# 1.net
KiCad netlist of a schematic drawn in Altium Designer
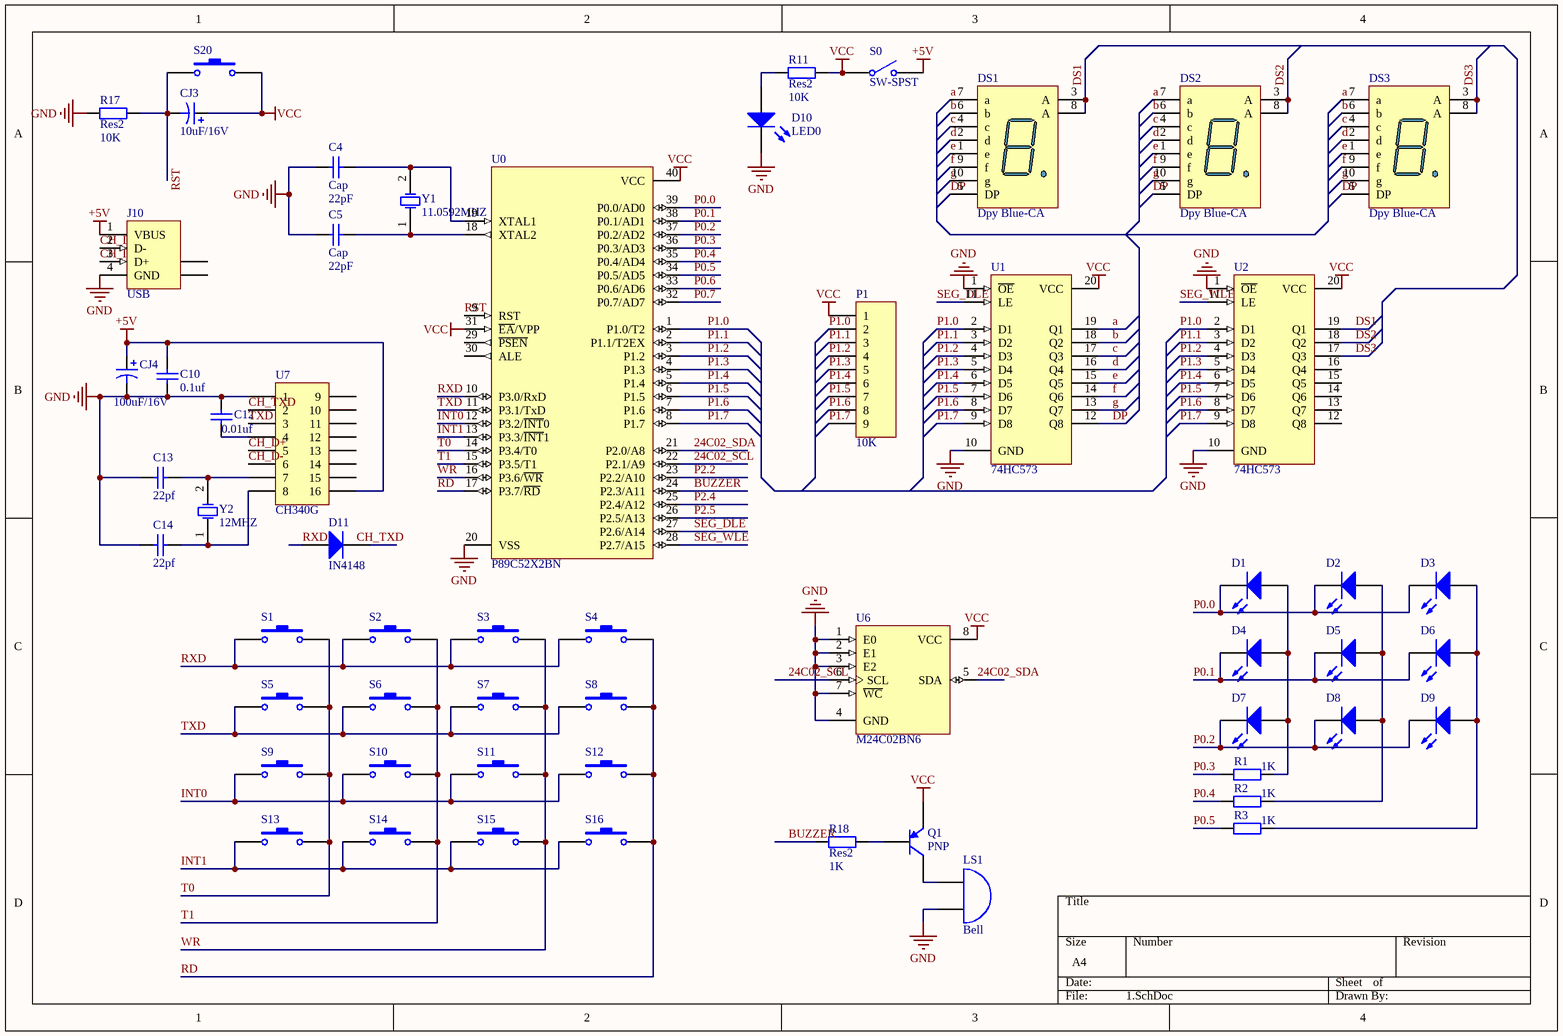
[diagram p0: 1.SchDoc]

(export (version "E")
  (design (tool "Eeschema 10.0.6"))
  (components
    (comp (ref "C4")
      (value "Cap")
      (footprint "RAD-0.3")
      (description "Capacitor")
      (fields (field (name "ALTIUM_VALUE") "22pF") (field (name "PUBLISHER") "Altium Limited"))
      (libsource (lib "Miscellaneous Devices") (part "Cap"))
    )
    (comp (ref "C5")
      (value "Cap")
      (footprint "RAD-0.3")
      (description "Capacitor")
      (fields (field (name "ALTIUM_VALUE") "22pF") (field (name "PUBLISHER") "Altium Limited"))
      (libsource (lib "Miscellaneous Devices") (part "Cap"))
    )
    (comp (ref "C10")
      (value "0.1uf")
      (footprint "RAD-0.3")
      (description "Capacitor")
      (fields (field (name "Comment") "Cap") (field (name "PUBLISHER") "Altium Limited"))
      (libsource (lib "Miscellaneous Devices") (part "Cap"))
    )
    (comp (ref "C12")
      (value "0.01uf")
      (footprint "RAD-0.3")
      (description "Capacitor")
      (fields (field (name "Comment") "Cap") (field (name "PUBLISHER") "Altium Limited"))
      (libsource (lib "Miscellaneous Devices") (part "Cap"))
    )
    (comp (ref "C13")
      (value "22pf")
      (footprint "RAD-0.3")
      (description "Capacitor")
      (fields (field (name "Comment") "Cap") (field (name "PUBLISHER") "Altium Limited"))
      (libsource (lib "Miscellaneous Devices") (part "Cap"))
    )
    (comp (ref "C14")
      (value "22pf")
      (footprint "RAD-0.3")
      (description "Capacitor")
      (fields (field (name "Comment") "Cap") (field (name "PUBLISHER") "Altium Limited"))
      (libsource (lib "Miscellaneous Devices") (part "Cap"))
    )
    (comp (ref "CJ3")
      (value "10uF/16V")
      (footprint "RB7.6-15")
      (description "Polarized Capacitor (Radial)")
      (fields (field (name "PUBLISHER") "Altium Limited"))
      (libsource (lib "Miscellaneous Devices") (part "Cap Pol1"))
    )
    (comp (ref "CJ4")
      (value "100uF/16V")
      (footprint "RB7.6-15")
      (description "Polarized Capacitor (Radial)")
      (fields (field (name "PUBLISHER") "Altium Limited"))
      (libsource (lib "Miscellaneous Devices") (part "Cap Pol1"))
    )
    (comp (ref "D1")
      (value "~")
      (footprint "LED-0")
      (description "Typical INFRARED GaAs LED")
      (fields (field (name "PUBLISHER") "Altium Limited"))
      (libsource (lib "Miscellaneous Devices") (part "LED0"))
    )
    (comp (ref "D2")
      (value "~")
      (footprint "LED-0")
      (description "Typical INFRARED GaAs LED")
      (fields (field (name "PUBLISHER") "Altium Limited"))
      (libsource (lib "Miscellaneous Devices") (part "LED0"))
    )
    (comp (ref "D3")
      (value "~")
      (footprint "LED-0")
      (description "Typical INFRARED GaAs LED")
      (fields (field (name "PUBLISHER") "Altium Limited"))
      (libsource (lib "Miscellaneous Devices") (part "LED0"))
    )
    (comp (ref "D4")
      (value "~")
      (footprint "LED-0")
      (description "Typical INFRARED GaAs LED")
      (fields (field (name "PUBLISHER") "Altium Limited"))
      (libsource (lib "Miscellaneous Devices") (part "LED0"))
    )
    (comp (ref "D5")
      (value "~")
      (footprint "LED-0")
      (description "Typical INFRARED GaAs LED")
      (fields (field (name "PUBLISHER") "Altium Limited"))
      (libsource (lib "Miscellaneous Devices") (part "LED0"))
    )
    (comp (ref "D6")
      (value "~")
      (footprint "LED-0")
      (description "Typical INFRARED GaAs LED")
      (fields (field (name "PUBLISHER") "Altium Limited"))
      (libsource (lib "Miscellaneous Devices") (part "LED0"))
    )
    (comp (ref "D7")
      (value "~")
      (footprint "LED-0")
      (description "Typical INFRARED GaAs LED")
      (fields (field (name "PUBLISHER") "Altium Limited"))
      (libsource (lib "Miscellaneous Devices") (part "LED0"))
    )
    (comp (ref "D8")
      (value "~")
      (footprint "LED-0")
      (description "Typical INFRARED GaAs LED")
      (fields (field (name "PUBLISHER") "Altium Limited"))
      (libsource (lib "Miscellaneous Devices") (part "LED0"))
    )
    (comp (ref "D9")
      (value "~")
      (footprint "LED-0")
      (description "Typical INFRARED GaAs LED")
      (fields (field (name "PUBLISHER") "Altium Limited"))
      (libsource (lib "Miscellaneous Devices") (part "LED0"))
    )
    (comp (ref "D10")
      (value "LED0")
      (footprint "LED-0")
      (description "Typical INFRARED GaAs LED")
      (fields (field (name "PUBLISHER") "Altium Limited"))
      (libsource (lib "Miscellaneous Devices") (part "LED0"))
    )
    (comp (ref "D11")
      (value "IN4148")
      (footprint "DO-35")
      (description "High Conductance Fast Diode")
      (fields (field (name "PUBLISHER") "Altium Limited"))
      (libsource (lib "Miscellaneous Devices") (part "Diode 1N914"))
    )
    (comp (ref "DS1")
      (value "Dpy Blue-CA")
      (footprint "H")
      (description "14.2 mm General Purpose Blue 7-Segment Display: CA, RH DP, Gray Surface")
      (fields (field (name "PUBLISHER") "Altium Limited"))
      (libsource (lib "Miscellaneous Devices") (part "Dpy Blue-CA"))
    )
    (comp (ref "DS2")
      (value "Dpy Blue-CA")
      (footprint "H")
      (description "14.2 mm General Purpose Blue 7-Segment Display: CA, RH DP, Gray Surface")
      (fields (field (name "PUBLISHER") "Altium Limited"))
      (libsource (lib "Miscellaneous Devices") (part "Dpy Blue-CA"))
    )
    (comp (ref "DS3")
      (value "Dpy Blue-CA")
      (footprint "H")
      (description "14.2 mm General Purpose Blue 7-Segment Display: CA, RH DP, Gray Surface")
      (fields (field (name "PUBLISHER") "Altium Limited"))
      (libsource (lib "Miscellaneous Devices") (part "Dpy Blue-CA"))
    )
    (comp (ref "J10")
      (value "USB")
      (footprint "787616")
      (description "USB 1.1, Right Angle, Thru-Hole, A Type, Receptacle, 4 Position, Natural")
      (fields (field (name "PUBLISHER") "Altium Limited"))
      (libsource (lib "AMP Serial Bus USB") (part "787616-5"))
    )
    (comp (ref "LS1")
      (value "Bell")
      (footprint "PIN2")
      (description "Electrical Bell")
      (fields (field (name "PUBLISHER") "Altium Limited"))
      (libsource (lib "Miscellaneous Devices") (part "Bell"))
    )
    (comp (ref "P1")
      (value "10K")
      (footprint "MHDR1X9")
      (description "Header, 9-Pin")
      (fields (field (name "PUBLISHER") "Altium Limited"))
      (libsource (lib "Miscellaneous Connectors") (part "MHDR1X9"))
    )
    (comp (ref "Q1")
      (value "PNP")
      (footprint "SOT-23B")
      (description "PNP Bipolar Transistor")
      (fields (field (name "PUBLISHER") "Altium Limited"))
      (libsource (lib "Miscellaneous Devices") (part "PNP"))
    )
    (comp (ref "R1")
      (value "1K")
      (footprint "AXIAL-0.4")
      (description "Resistor")
      (fields (field (name "PUBLISHER") "Altium Limited"))
      (libsource (lib "Miscellaneous Devices") (part "Res2"))
    )
    (comp (ref "R2")
      (value "1K")
      (footprint "AXIAL-0.4")
      (description "Resistor")
      (fields (field (name "PUBLISHER") "Altium Limited"))
      (libsource (lib "Miscellaneous Devices") (part "Res2"))
    )
    (comp (ref "R3")
      (value "1K")
      (footprint "AXIAL-0.4")
      (description "Resistor")
      (fields (field (name "PUBLISHER") "Altium Limited"))
      (libsource (lib "Miscellaneous Devices") (part "Res2"))
    )
    (comp (ref "R11")
      (value "Res2")
      (footprint "AXIAL-0.4")
      (description "Resistor")
      (fields (field (name "ALTIUM_VALUE") "10K") (field (name "PUBLISHER") "Altium Limited"))
      (libsource (lib "Miscellaneous Devices") (part "Res2"))
    )
    (comp (ref "R17")
      (value "Res2")
      (footprint "AXIAL-0.4")
      (description "Resistor")
      (fields (field (name "ALTIUM_VALUE") "10K") (field (name "PUBLISHER") "Altium Limited"))
      (libsource (lib "") (part "Res2_1"))
    )
    (comp (ref "R18")
      (value "Res2")
      (footprint "AXIAL-0.4")
      (description "Resistor")
      (fields (field (name "ALTIUM_VALUE") "1K") (field (name "PUBLISHER") "Altium Limited"))
      (libsource (lib "Miscellaneous Devices") (part "Res2"))
    )
    (comp (ref "S0")
      (value "SW-SPST")
      (footprint "SPST-2")
      (description "Single-Pole, Single-Throw Switch")
      (fields (field (name "PUBLISHER") "Altium Limited"))
      (libsource (lib "Miscellaneous Devices") (part "SW-SPST"))
    )
    (comp (ref "S1")
      (value "~")
      (footprint "SPST-2")
      (description "Switch")
      (fields (field (name "PUBLISHER") "Altium Limited"))
      (libsource (lib "Miscellaneous Devices") (part "SW-PB"))
    )
    (comp (ref "S2")
      (value "~")
      (footprint "SPST-2")
      (description "Switch")
      (fields (field (name "PUBLISHER") "Altium Limited"))
      (libsource (lib "Miscellaneous Devices") (part "SW-PB"))
    )
    (comp (ref "S3")
      (value "~")
      (footprint "SPST-2")
      (description "Switch")
      (fields (field (name "PUBLISHER") "Altium Limited"))
      (libsource (lib "Miscellaneous Devices") (part "SW-PB"))
    )
    (comp (ref "S4")
      (value "~")
      (footprint "SPST-2")
      (description "Switch")
      (fields (field (name "PUBLISHER") "Altium Limited"))
      (libsource (lib "Miscellaneous Devices") (part "SW-PB"))
    )
    (comp (ref "S5")
      (value "~")
      (footprint "SPST-2")
      (description "Switch")
      (fields (field (name "PUBLISHER") "Altium Limited"))
      (libsource (lib "Miscellaneous Devices") (part "SW-PB"))
    )
    (comp (ref "S6")
      (value "~")
      (footprint "SPST-2")
      (description "Switch")
      (fields (field (name "PUBLISHER") "Altium Limited"))
      (libsource (lib "Miscellaneous Devices") (part "SW-PB"))
    )
    (comp (ref "S7")
      (value "~")
      (footprint "SPST-2")
      (description "Switch")
      (fields (field (name "PUBLISHER") "Altium Limited"))
      (libsource (lib "Miscellaneous Devices") (part "SW-PB"))
    )
    (comp (ref "S8")
      (value "~")
      (footprint "SPST-2")
      (description "Switch")
      (fields (field (name "PUBLISHER") "Altium Limited"))
      (libsource (lib "Miscellaneous Devices") (part "SW-PB"))
    )
    (comp (ref "S9")
      (value "~")
      (footprint "SPST-2")
      (description "Switch")
      (fields (field (name "PUBLISHER") "Altium Limited"))
      (libsource (lib "Miscellaneous Devices") (part "SW-PB"))
    )
    (comp (ref "S10")
      (value "~")
      (footprint "SPST-2")
      (description "Switch")
      (fields (field (name "PUBLISHER") "Altium Limited"))
      (libsource (lib "Miscellaneous Devices") (part "SW-PB"))
    )
    (comp (ref "S11")
      (value "~")
      (footprint "SPST-2")
      (description "Switch")
      (fields (field (name "PUBLISHER") "Altium Limited"))
      (libsource (lib "Miscellaneous Devices") (part "SW-PB"))
    )
    (comp (ref "S12")
      (value "~")
      (footprint "SPST-2")
      (description "Switch")
      (fields (field (name "PUBLISHER") "Altium Limited"))
      (libsource (lib "Miscellaneous Devices") (part "SW-PB"))
    )
    (comp (ref "S13")
      (value "~")
      (footprint "SPST-2")
      (description "Switch")
      (fields (field (name "PUBLISHER") "Altium Limited"))
      (libsource (lib "Miscellaneous Devices") (part "SW-PB"))
    )
    (comp (ref "S14")
      (value "~")
      (footprint "SPST-2")
      (description "Switch")
      (fields (field (name "PUBLISHER") "Altium Limited"))
      (libsource (lib "Miscellaneous Devices") (part "SW-PB"))
    )
    (comp (ref "S15")
      (value "~")
      (footprint "SPST-2")
      (description "Switch")
      (fields (field (name "PUBLISHER") "Altium Limited"))
      (libsource (lib "Miscellaneous Devices") (part "SW-PB"))
    )
    (comp (ref "S16")
      (value "~")
      (footprint "SPST-2")
      (description "Switch")
      (fields (field (name "PUBLISHER") "Altium Limited"))
      (libsource (lib "Miscellaneous Devices") (part "SW-PB"))
    )
    (comp (ref "S20")
      (value "~")
      (footprint "SPST-2")
      (description "Switch")
      (fields (field (name "PUBLISHER") "Altium Limited"))
      (libsource (lib "Miscellaneous Devices") (part "SW-PB"))
    )
    (comp (ref "U0")
      (value "P89C52X2BN")
      (footprint "SOT129-1")
      (description "80C51 8-Bit Flash Microcontroller Family, 8 kB Flash")
      (fields (field (name "PUBLISHER") "Altium Limited"))
      (libsource (lib "Philips Microcontroller 8-Bit") (part "P89C52X2BN"))
    )
    (comp (ref "U1")
      (value "74HC573")
      (footprint "FK020")
      (description "Octal Transparent D-Type Latch with 3-State Outputs")
      (fields (field (name "PUBLISHER") "Altium Limited"))
      (libsource (lib "TI Logic Latch") (part "SNJ54AHC573FK"))
    )
    (comp (ref "U2")
      (value "74HC573")
      (footprint "FK020")
      (description "Octal Transparent D-Type Latch with 3-State Outputs")
      (fields (field (name "PUBLISHER") "Altium Limited"))
      (libsource (lib "TI Logic Latch") (part "SNJ54AHC573FK"))
    )
    (comp (ref "U6")
      (value "M24C02BN6")
      (footprint "PSDIP8A")
      (description "2Kbit Serial I²C Bus EEPROM")
      (fields (field (name "PUBLISHER") "Altium Limited"))
      (libsource (lib "ST Memory EEPROM Serial") (part "M24C02BN6"))
    )
    (comp (ref "U7")
      (value "CH340G")
      (footprint "HDR2X8_CEN")
      (description "Header, 8-Pin, Dual row")
      (fields (field (name "PUBLISHER") "Altium Limited"))
      (libsource (lib "Miscellaneous Connectors") (part "Header 8X2A"))
    )
    (comp (ref "Y1")
      (value "11.0592MHZ")
      (footprint "R38")
      (description "Crystal Oscillator")
      (fields (field (name "PUBLISHER") "Altium Limited"))
      (libsource (lib "Miscellaneous Devices") (part "XTAL"))
    )
    (comp (ref "Y2")
      (value "12MHZ")
      (footprint "R38")
      (description "Crystal Oscillator")
      (fields (field (name "PUBLISHER") "Altium Limited"))
      (libsource (lib "Miscellaneous Devices") (part "XTAL"))
    )
  )
  (nets
    (net (code "1") (name "+5V") (class "Default")
      (node (ref "C10") (pin "1") (pinfunction "1_1") (pintype "passive"))
      (node (ref "CJ4") (pin "1") (pinfunction "1_1") (pintype "passive"))
      (node (ref "J10") (pin "1") (pinfunction "VBUS_1") (pintype "power_in"))
      (node (ref "S0") (pin "2") (pinfunction "NO_2") (pintype "passive"))
      (node (ref "U7") (pin "16") (pinfunction "16_16") (pintype "passive"))
    )
    (net (code "2") (name "/24C02_SCL") (class "Default")
      (node (ref "U0") (pin "22") (pinfunction "P2.1/A9_22") (pintype "bidirectional"))
      (node (ref "U6") (pin "6") (pinfunction "SCL_6") (pintype "input"))
    )
    (net (code "3") (name "/24C02_SDA") (class "Default")
      (node (ref "U0") (pin "21") (pinfunction "P2.0/A8_21") (pintype "bidirectional"))
      (node (ref "U6") (pin "5") (pinfunction "SDA_5") (pintype "bidirectional"))
    )
    (net (code "4") (name "/BUZZER") (class "Default")
      (node (ref "R18") (pin "2") (pinfunction "2_2") (pintype "passive"))
      (node (ref "U0") (pin "24") (pinfunction "P2.3/A11_24") (pintype "bidirectional"))
    )
    (net (code "5") (name "/CH_D+") (class "Default")
      (node (ref "J10") (pin "3") (pinfunction "D+_3") (pintype "input"))
      (node (ref "U7") (pin "5") (pinfunction "5_5") (pintype "passive"))
    )
    (net (code "6") (name "/CH_D-") (class "Default")
      (node (ref "J10") (pin "2") (pinfunction "D-_2") (pintype "input"))
      (node (ref "U7") (pin "6") (pinfunction "6_6") (pintype "passive"))
    )
    (net (code "7") (name "/CH_TXD") (class "Default")
      (node (ref "U7") (pin "2") (pinfunction "2_2") (pintype "passive"))
    )
    (net (code "8") (name "/DP") (class "Default")
      (node (ref "DS1") (pin "5") (pinfunction "DP_5") (pintype "passive"))
      (node (ref "DS2") (pin "5") (pinfunction "DP_5") (pintype "passive"))
      (node (ref "DS3") (pin "5") (pinfunction "DP_5") (pintype "passive"))
      (node (ref "U1") (pin "12") (pinfunction "Q8_12") (pintype "tri_state"))
    )
    (net (code "9") (name "/DS1") (class "Default")
      (node (ref "DS1") (pin "3") (pinfunction "A_3") (pintype "passive"))
      (node (ref "DS1") (pin "8") (pinfunction "A_8") (pintype "passive"))
      (node (ref "U2") (pin "19") (pinfunction "Q1_19") (pintype "tri_state"))
    )
    (net (code "10") (name "/DS2") (class "Default")
      (node (ref "DS2") (pin "3") (pinfunction "A_3") (pintype "passive"))
      (node (ref "DS2") (pin "8") (pinfunction "A_8") (pintype "passive"))
      (node (ref "U2") (pin "18") (pinfunction "Q2_18") (pintype "tri_state"))
    )
    (net (code "11") (name "/DS3") (class "Default")
      (node (ref "DS3") (pin "3") (pinfunction "A_3") (pintype "passive"))
      (node (ref "DS3") (pin "8") (pinfunction "A_8") (pintype "passive"))
      (node (ref "U2") (pin "17") (pinfunction "Q3_17") (pintype "tri_state"))
    )
    (net (code "12") (name "/INT0") (class "Default")
      (node (ref "S10") (pin "1") (pinfunction "1_1") (pintype "passive"))
      (node (ref "S11") (pin "1") (pinfunction "1_1") (pintype "passive"))
      (node (ref "S12") (pin "1") (pinfunction "1_1") (pintype "passive"))
      (node (ref "S9") (pin "1") (pinfunction "1_1") (pintype "passive"))
      (node (ref "U0") (pin "12") (pinfunction "P3.2/~{INT}0_12") (pintype "bidirectional"))
    )
    (net (code "13") (name "/INT1") (class "Default")
      (node (ref "S13") (pin "1") (pinfunction "1_1") (pintype "passive"))
      (node (ref "S14") (pin "1") (pinfunction "1_1") (pintype "passive"))
      (node (ref "S15") (pin "1") (pinfunction "1_1") (pintype "passive"))
      (node (ref "S16") (pin "1") (pinfunction "1_1") (pintype "passive"))
      (node (ref "U0") (pin "13") (pinfunction "P3.3/~{INT}1_13") (pintype "bidirectional"))
    )
    (net (code "14") (name "/P0.0") (class "Default")
      (node (ref "D1") (pin "2") (pinfunction "K_2") (pintype "passive"))
      (node (ref "D2") (pin "2") (pinfunction "K_2") (pintype "passive"))
      (node (ref "D3") (pin "2") (pinfunction "K_2") (pintype "passive"))
      (node (ref "U0") (pin "39") (pinfunction "P0.0/AD0_39") (pintype "bidirectional"))
    )
    (net (code "15") (name "/P0.1") (class "Default")
      (node (ref "D4") (pin "2") (pinfunction "K_2") (pintype "passive"))
      (node (ref "D5") (pin "2") (pinfunction "K_2") (pintype "passive"))
      (node (ref "D6") (pin "2") (pinfunction "K_2") (pintype "passive"))
      (node (ref "U0") (pin "38") (pinfunction "P0.1/AD1_38") (pintype "bidirectional"))
    )
    (net (code "16") (name "/P0.2") (class "Default")
      (node (ref "D7") (pin "2") (pinfunction "K_2") (pintype "passive"))
      (node (ref "D8") (pin "2") (pinfunction "K_2") (pintype "passive"))
      (node (ref "D9") (pin "2") (pinfunction "K_2") (pintype "passive"))
      (node (ref "U0") (pin "37") (pinfunction "P0.2/AD2_37") (pintype "bidirectional"))
    )
    (net (code "17") (name "/P0.3") (class "Default")
      (node (ref "R1") (pin "2") (pinfunction "2_2") (pintype "passive"))
      (node (ref "U0") (pin "36") (pinfunction "P0.3/AD3_36") (pintype "bidirectional"))
    )
    (net (code "18") (name "/P0.4") (class "Default")
      (node (ref "R2") (pin "2") (pinfunction "2_2") (pintype "passive"))
      (node (ref "U0") (pin "35") (pinfunction "P0.4/AD4_35") (pintype "bidirectional"))
    )
    (net (code "19") (name "/P0.5") (class "Default")
      (node (ref "R3") (pin "2") (pinfunction "2_2") (pintype "passive"))
      (node (ref "U0") (pin "34") (pinfunction "P0.5/AD5_34") (pintype "bidirectional"))
    )
    (net (code "20") (name "/P0.6") (class "Default")
      (node (ref "U0") (pin "33") (pinfunction "P0.6/AD6_33") (pintype "bidirectional"))
    )
    (net (code "21") (name "/P0.7") (class "Default")
      (node (ref "U0") (pin "32") (pinfunction "P0.7/AD7_32") (pintype "bidirectional"))
    )
    (net (code "22") (name "/P1.0") (class "Default")
      (node (ref "P1") (pin "2") (pinfunction "2_2") (pintype "passive"))
      (node (ref "U0") (pin "1") (pinfunction "P1.0/T2_1") (pintype "bidirectional"))
      (node (ref "U1") (pin "2") (pinfunction "D1_2") (pintype "input"))
      (node (ref "U2") (pin "2") (pinfunction "D1_2") (pintype "input"))
    )
    (net (code "23") (name "/P1.1") (class "Default")
      (node (ref "P1") (pin "3") (pinfunction "3_3") (pintype "passive"))
      (node (ref "U0") (pin "2") (pinfunction "P1.1/T2EX_2") (pintype "bidirectional"))
      (node (ref "U1") (pin "3") (pinfunction "D2_3") (pintype "input"))
      (node (ref "U2") (pin "3") (pinfunction "D2_3") (pintype "input"))
    )
    (net (code "24") (name "/P1.2") (class "Default")
      (node (ref "P1") (pin "4") (pinfunction "4_4") (pintype "passive"))
      (node (ref "U0") (pin "3") (pinfunction "P1.2_3") (pintype "bidirectional"))
      (node (ref "U1") (pin "4") (pinfunction "D3_4") (pintype "input"))
      (node (ref "U2") (pin "4") (pinfunction "D3_4") (pintype "input"))
    )
    (net (code "25") (name "/P1.3") (class "Default")
      (node (ref "P1") (pin "5") (pinfunction "5_5") (pintype "passive"))
      (node (ref "U0") (pin "4") (pinfunction "P1.3_4") (pintype "bidirectional"))
      (node (ref "U1") (pin "5") (pinfunction "D4_5") (pintype "input"))
      (node (ref "U2") (pin "5") (pinfunction "D4_5") (pintype "input"))
    )
    (net (code "26") (name "/P1.4") (class "Default")
      (node (ref "P1") (pin "6") (pinfunction "6_6") (pintype "passive"))
      (node (ref "U0") (pin "5") (pinfunction "P1.4_5") (pintype "bidirectional"))
      (node (ref "U1") (pin "6") (pinfunction "D5_6") (pintype "input"))
      (node (ref "U2") (pin "6") (pinfunction "D5_6") (pintype "input"))
    )
    (net (code "27") (name "/P1.5") (class "Default")
      (node (ref "P1") (pin "7") (pinfunction "7_7") (pintype "passive"))
      (node (ref "U0") (pin "6") (pinfunction "P1.5_6") (pintype "bidirectional"))
      (node (ref "U1") (pin "7") (pinfunction "D6_7") (pintype "input"))
      (node (ref "U2") (pin "7") (pinfunction "D6_7") (pintype "input"))
    )
    (net (code "28") (name "/P1.6") (class "Default")
      (node (ref "P1") (pin "8") (pinfunction "8_8") (pintype "passive"))
      (node (ref "U0") (pin "7") (pinfunction "P1.6_7") (pintype "bidirectional"))
      (node (ref "U1") (pin "8") (pinfunction "D7_8") (pintype "input"))
      (node (ref "U2") (pin "8") (pinfunction "D7_8") (pintype "input"))
    )
    (net (code "29") (name "/P1.7") (class "Default")
      (node (ref "P1") (pin "9") (pinfunction "9_9") (pintype "passive"))
      (node (ref "U0") (pin "8") (pinfunction "P1.7_8") (pintype "bidirectional"))
      (node (ref "U1") (pin "9") (pinfunction "D8_9") (pintype "input"))
      (node (ref "U2") (pin "9") (pinfunction "D8_9") (pintype "input"))
    )
    (net (code "30") (name "/P2.2") (class "Default")
      (node (ref "U0") (pin "23") (pinfunction "P2.2/A10_23") (pintype "bidirectional"))
    )
    (net (code "31") (name "/P2.4") (class "Default")
      (node (ref "U0") (pin "25") (pinfunction "P2.4/A12_25") (pintype "bidirectional"))
    )
    (net (code "32") (name "/P2.5") (class "Default")
      (node (ref "U0") (pin "26") (pinfunction "P2.5/A13_26") (pintype "bidirectional"))
    )
    (net (code "33") (name "/RD") (class "Default")
      (node (ref "S12") (pin "2") (pinfunction "2_2") (pintype "passive"))
      (node (ref "S16") (pin "2") (pinfunction "2_2") (pintype "passive"))
      (node (ref "S4") (pin "2") (pinfunction "2_2") (pintype "passive"))
      (node (ref "S8") (pin "2") (pinfunction "2_2") (pintype "passive"))
      (node (ref "U0") (pin "17") (pinfunction "P3.7/~{RD}_17") (pintype "bidirectional"))
    )
    (net (code "34") (name "/RST") (class "Default")
      (node (ref "CJ3") (pin "2") (pinfunction "2_2") (pintype "passive"))
      (node (ref "R17") (pin "2") (pinfunction "2_2") (pintype "passive"))
      (node (ref "S20") (pin "1") (pinfunction "1_1") (pintype "passive"))
      (node (ref "U0") (pin "9") (pinfunction "RST_9") (pintype "input"))
    )
    (net (code "35") (name "/RXD") (class "Default")
      (node (ref "D11") (pin "1") (pinfunction "A_1") (pintype "passive"))
      (node (ref "S1") (pin "1") (pinfunction "1_1") (pintype "passive"))
      (node (ref "S2") (pin "1") (pinfunction "1_1") (pintype "passive"))
      (node (ref "S3") (pin "1") (pinfunction "1_1") (pintype "passive"))
      (node (ref "S4") (pin "1") (pinfunction "1_1") (pintype "passive"))
      (node (ref "U0") (pin "10") (pinfunction "P3.0/RxD_10") (pintype "bidirectional"))
    )
    (net (code "36") (name "/SEG_DLE") (class "Default")
      (node (ref "U0") (pin "27") (pinfunction "P2.6/A14_27") (pintype "bidirectional"))
      (node (ref "U1") (pin "11") (pinfunction "LE_11") (pintype "input"))
    )
    (net (code "37") (name "/SEG_WLE") (class "Default")
      (node (ref "U0") (pin "28") (pinfunction "P2.7/A15_28") (pintype "bidirectional"))
      (node (ref "U2") (pin "11") (pinfunction "LE_11") (pintype "input"))
    )
    (net (code "38") (name "/T0") (class "Default")
      (node (ref "S1") (pin "2") (pinfunction "2_2") (pintype "passive"))
      (node (ref "S13") (pin "2") (pinfunction "2_2") (pintype "passive"))
      (node (ref "S5") (pin "2") (pinfunction "2_2") (pintype "passive"))
      (node (ref "S9") (pin "2") (pinfunction "2_2") (pintype "passive"))
      (node (ref "U0") (pin "14") (pinfunction "P3.4/T0_14") (pintype "bidirectional"))
    )
    (net (code "39") (name "/T1") (class "Default")
      (node (ref "S10") (pin "2") (pinfunction "2_2") (pintype "passive"))
      (node (ref "S14") (pin "2") (pinfunction "2_2") (pintype "passive"))
      (node (ref "S2") (pin "2") (pinfunction "2_2") (pintype "passive"))
      (node (ref "S6") (pin "2") (pinfunction "2_2") (pintype "passive"))
      (node (ref "U0") (pin "15") (pinfunction "P3.5/T1_15") (pintype "bidirectional"))
    )
    (net (code "40") (name "/TXD") (class "Default")
      (node (ref "S5") (pin "1") (pinfunction "1_1") (pintype "passive"))
      (node (ref "S6") (pin "1") (pinfunction "1_1") (pintype "passive"))
      (node (ref "S7") (pin "1") (pinfunction "1_1") (pintype "passive"))
      (node (ref "S8") (pin "1") (pinfunction "1_1") (pintype "passive"))
      (node (ref "U0") (pin "11") (pinfunction "P3.1/TxD_11") (pintype "bidirectional"))
      (node (ref "U7") (pin "3") (pinfunction "3_3") (pintype "passive"))
    )
    (net (code "41") (name "/WR") (class "Default")
      (node (ref "S11") (pin "2") (pinfunction "2_2") (pintype "passive"))
      (node (ref "S15") (pin "2") (pinfunction "2_2") (pintype "passive"))
      (node (ref "S3") (pin "2") (pinfunction "2_2") (pintype "passive"))
      (node (ref "S7") (pin "2") (pinfunction "2_2") (pintype "passive"))
      (node (ref "U0") (pin "16") (pinfunction "P3.6/~{WR}_16") (pintype "bidirectional"))
    )
    (net (code "42") (name "/a") (class "Default")
      (node (ref "DS1") (pin "7") (pinfunction "a_7") (pintype "passive"))
      (node (ref "DS2") (pin "7") (pinfunction "a_7") (pintype "passive"))
      (node (ref "DS3") (pin "7") (pinfunction "a_7") (pintype "passive"))
      (node (ref "U1") (pin "19") (pinfunction "Q1_19") (pintype "tri_state"))
    )
    (net (code "43") (name "/b") (class "Default")
      (node (ref "DS1") (pin "6") (pinfunction "b_6") (pintype "passive"))
      (node (ref "DS2") (pin "6") (pinfunction "b_6") (pintype "passive"))
      (node (ref "DS3") (pin "6") (pinfunction "b_6") (pintype "passive"))
      (node (ref "U1") (pin "18") (pinfunction "Q2_18") (pintype "tri_state"))
    )
    (net (code "44") (name "/c") (class "Default")
      (node (ref "DS1") (pin "4") (pinfunction "c_4") (pintype "passive"))
      (node (ref "DS2") (pin "4") (pinfunction "c_4") (pintype "passive"))
      (node (ref "DS3") (pin "4") (pinfunction "c_4") (pintype "passive"))
      (node (ref "U1") (pin "17") (pinfunction "Q3_17") (pintype "tri_state"))
    )
    (net (code "45") (name "/d") (class "Default")
      (node (ref "DS1") (pin "2") (pinfunction "d_2") (pintype "passive"))
      (node (ref "DS2") (pin "2") (pinfunction "d_2") (pintype "passive"))
      (node (ref "DS3") (pin "2") (pinfunction "d_2") (pintype "passive"))
      (node (ref "U1") (pin "16") (pinfunction "Q4_16") (pintype "tri_state"))
    )
    (net (code "46") (name "/e") (class "Default")
      (node (ref "DS1") (pin "1") (pinfunction "e_1") (pintype "passive"))
      (node (ref "DS2") (pin "1") (pinfunction "e_1") (pintype "passive"))
      (node (ref "DS3") (pin "1") (pinfunction "e_1") (pintype "passive"))
      (node (ref "U1") (pin "15") (pinfunction "Q5_15") (pintype "tri_state"))
    )
    (net (code "47") (name "/f") (class "Default")
      (node (ref "DS1") (pin "9") (pinfunction "f_9") (pintype "passive"))
      (node (ref "DS2") (pin "9") (pinfunction "f_9") (pintype "passive"))
      (node (ref "DS3") (pin "9") (pinfunction "f_9") (pintype "passive"))
      (node (ref "U1") (pin "14") (pinfunction "Q6_14") (pintype "tri_state"))
    )
    (net (code "48") (name "/g") (class "Default")
      (node (ref "DS1") (pin "10") (pinfunction "g_10") (pintype "passive"))
      (node (ref "DS2") (pin "10") (pinfunction "g_10") (pintype "passive"))
      (node (ref "DS3") (pin "10") (pinfunction "g_10") (pintype "passive"))
      (node (ref "U1") (pin "13") (pinfunction "Q7_13") (pintype "tri_state"))
    )
    (net (code "49") (name "GND") (class "Default")
      (node (ref "C10") (pin "2") (pinfunction "2_2") (pintype "passive"))
      (node (ref "C12") (pin "2") (pinfunction "2_2") (pintype "passive"))
      (node (ref "C13") (pin "2") (pinfunction "2_2") (pintype "passive"))
      (node (ref "C14") (pin "2") (pinfunction "2_2") (pintype "passive"))
      (node (ref "C4") (pin "1") (pinfunction "1_1") (pintype "passive"))
      (node (ref "C5") (pin "1") (pinfunction "1_1") (pintype "passive"))
      (node (ref "CJ4") (pin "2") (pinfunction "2_2") (pintype "passive"))
      (node (ref "D10") (pin "2") (pinfunction "K_2") (pintype "passive"))
      (node (ref "J10") (pin "4") (pinfunction "GND_4") (pintype "power_in"))
      (node (ref "LS1") (pin "2") (pinfunction "B_2") (pintype "passive"))
      (node (ref "R17") (pin "1") (pinfunction "1_1") (pintype "passive"))
      (node (ref "U0") (pin "20") (pinfunction "VSS_20") (pintype "power_in"))
      (node (ref "U1") (pin "1") (pinfunction "~{OE}_1") (pintype "input"))
      (node (ref "U1") (pin "10") (pinfunction "GND_10") (pintype "power_in"))
      (node (ref "U2") (pin "1") (pinfunction "~{OE}_1") (pintype "input"))
      (node (ref "U2") (pin "10") (pinfunction "GND_10") (pintype "power_in"))
      (node (ref "U6") (pin "1") (pinfunction "E0_1") (pintype "input"))
      (node (ref "U6") (pin "2") (pinfunction "E1_2") (pintype "input"))
      (node (ref "U6") (pin "3") (pinfunction "E2_3") (pintype "input"))
      (node (ref "U6") (pin "4") (pinfunction "GND_4") (pintype "power_in"))
      (node (ref "U6") (pin "7") (pinfunction "~{WC}_7") (pintype "input"))
      (node (ref "U7") (pin "1") (pinfunction "1_1") (pintype "passive"))
    )
    (net (code "50") (name "Net-(C12-Pad1)") (class "Default")
      (node (ref "C12") (pin "1") (pinfunction "1_1") (pintype "passive"))
      (node (ref "U7") (pin "4") (pinfunction "4_4") (pintype "passive"))
    )
    (net (code "51") (name "Net-(D1-A)") (class "Default")
      (node (ref "D1") (pin "1") (pinfunction "A_1") (pintype "passive"))
      (node (ref "D4") (pin "1") (pinfunction "A_1") (pintype "passive"))
      (node (ref "D7") (pin "1") (pinfunction "A_1") (pintype "passive"))
      (node (ref "R1") (pin "1") (pinfunction "1_1") (pintype "passive"))
    )
    (net (code "52") (name "Net-(D2-A)") (class "Default")
      (node (ref "D2") (pin "1") (pinfunction "A_1") (pintype "passive"))
      (node (ref "D5") (pin "1") (pinfunction "A_1") (pintype "passive"))
      (node (ref "D8") (pin "1") (pinfunction "A_1") (pintype "passive"))
      (node (ref "R2") (pin "1") (pinfunction "1_1") (pintype "passive"))
    )
    (net (code "53") (name "Net-(D3-A)") (class "Default")
      (node (ref "D3") (pin "1") (pinfunction "A_1") (pintype "passive"))
      (node (ref "D6") (pin "1") (pinfunction "A_1") (pintype "passive"))
      (node (ref "D9") (pin "1") (pinfunction "A_1") (pintype "passive"))
      (node (ref "R3") (pin "1") (pinfunction "1_1") (pintype "passive"))
    )
    (net (code "54") (name "Net-(D10-A)") (class "Default")
      (node (ref "D10") (pin "1") (pinfunction "A_1") (pintype "passive"))
      (node (ref "R11") (pin "2") (pinfunction "2_2") (pintype "passive"))
    )
    (net (code "55") (name "Net-(LS1-A)") (class "Default")
      (node (ref "LS1") (pin "1") (pinfunction "A_1") (pintype "passive"))
      (node (ref "Q1") (pin "1") (pinfunction "C_1") (pintype "passive"))
    )
    (net (code "56") (name "Net-(Q1-B)") (class "Default")
      (node (ref "Q1") (pin "2") (pinfunction "B_2") (pintype "passive"))
      (node (ref "R18") (pin "1") (pinfunction "1_1") (pintype "passive"))
    )
    (net (code "57") (name "Net-(U0-XTAL1)") (class "Default")
      (node (ref "C4") (pin "2") (pinfunction "2_2") (pintype "passive"))
      (node (ref "U0") (pin "19") (pinfunction "XTAL1_19") (pintype "input"))
      (node (ref "Y1") (pin "2") (pinfunction "OSC2_2") (pintype "passive"))
    )
    (net (code "58") (name "Net-(U0-XTAL2)") (class "Default")
      (node (ref "C5") (pin "2") (pinfunction "2_2") (pintype "passive"))
      (node (ref "U0") (pin "18") (pinfunction "XTAL2_18") (pintype "output"))
      (node (ref "Y1") (pin "1") (pinfunction "OSC1_1") (pintype "passive"))
    )
    (net (code "59") (name "Net-(Y2-OSC1)") (class "Default")
      (node (ref "C14") (pin "1") (pinfunction "1_1") (pintype "passive"))
      (node (ref "U7") (pin "8") (pinfunction "8_8") (pintype "passive"))
      (node (ref "Y2") (pin "1") (pinfunction "OSC1_1") (pintype "passive"))
    )
    (net (code "60") (name "Net-(Y2-OSC2)") (class "Default")
      (node (ref "C13") (pin "1") (pinfunction "1_1") (pintype "passive"))
      (node (ref "U7") (pin "7") (pinfunction "7_7") (pintype "passive"))
      (node (ref "Y2") (pin "2") (pinfunction "OSC2_2") (pintype "passive"))
    )
    (net (code "61") (name "VCC") (class "Default")
      (node (ref "CJ3") (pin "1") (pinfunction "1_1") (pintype "passive"))
      (node (ref "P1") (pin "1") (pinfunction "1_1") (pintype "passive"))
      (node (ref "Q1") (pin "3") (pinfunction "E_3") (pintype "passive"))
      (node (ref "R11") (pin "1") (pinfunction "1_1") (pintype "passive"))
      (node (ref "S0") (pin "1") (pinfunction "COMMON_1") (pintype "passive"))
      (node (ref "S20") (pin "2") (pinfunction "2_2") (pintype "passive"))
      (node (ref "U0") (pin "31") (pinfunction "~{EA}/VPP_31") (pintype "input"))
      (node (ref "U0") (pin "40") (pinfunction "VCC_40") (pintype "power_in"))
      (node (ref "U1") (pin "20") (pinfunction "VCC_20") (pintype "power_in"))
      (node (ref "U2") (pin "20") (pinfunction "VCC_20") (pintype "power_in"))
      (node (ref "U6") (pin "8") (pinfunction "VCC_8") (pintype "power_in"))
    )
    (net (code "62") (name "unconnected-(D11-K-Pad2)") (class "Default")
      (node (ref "D11") (pin "2") (pinfunction "K_2") (pintype "passive"))
    )
    (net (code "63") (name "unconnected-(J10-SHLD-Pad5)") (class "Default")
      (node (ref "J10") (pin "5") (pinfunction "SHLD_5") (pintype "passive"))
    )
    (net (code "64") (name "unconnected-(J10-SHLD-Pad6)") (class "Default")
      (node (ref "J10") (pin "6") (pinfunction "SHLD_6") (pintype "passive"))
    )
    (net (code "65") (name "unconnected-(U0-ALE-Pad30)") (class "Default")
      (node (ref "U0") (pin "30") (pinfunction "ALE_30") (pintype "output"))
    )
    (net (code "66") (name "unconnected-(U0-~{PSEN}-Pad29)") (class "Default")
      (node (ref "U0") (pin "29") (pinfunction "~{PSEN}_29") (pintype "output"))
    )
    (net (code "67") (name "unconnected-(U2-Q4-Pad16)") (class "Default")
      (node (ref "U2") (pin "16") (pinfunction "Q4_16") (pintype "tri_state"))
    )
    (net (code "68") (name "unconnected-(U2-Q5-Pad15)") (class "Default")
      (node (ref "U2") (pin "15") (pinfunction "Q5_15") (pintype "tri_state"))
    )
    (net (code "69") (name "unconnected-(U2-Q6-Pad14)") (class "Default")
      (node (ref "U2") (pin "14") (pinfunction "Q6_14") (pintype "tri_state"))
    )
    (net (code "70") (name "unconnected-(U2-Q7-Pad13)") (class "Default")
      (node (ref "U2") (pin "13") (pinfunction "Q7_13") (pintype "tri_state"))
    )
    (net (code "71") (name "unconnected-(U2-Q8-Pad12)") (class "Default")
      (node (ref "U2") (pin "12") (pinfunction "Q8_12") (pintype "tri_state"))
    )
    (net (code "72") (name "unconnected-(U7-Pad9)") (class "Default")
      (node (ref "U7") (pin "9") (pinfunction "9_9") (pintype "passive"))
    )
    (net (code "73") (name "unconnected-(U7-Pad10)") (class "Default")
      (node (ref "U7") (pin "10") (pinfunction "10_10") (pintype "passive"))
    )
    (net (code "74") (name "unconnected-(U7-Pad11)") (class "Default")
      (node (ref "U7") (pin "11") (pinfunction "11_11") (pintype "passive"))
    )
    (net (code "75") (name "unconnected-(U7-Pad12)") (class "Default")
      (node (ref "U7") (pin "12") (pinfunction "12_12") (pintype "passive"))
    )
    (net (code "76") (name "unconnected-(U7-Pad13)") (class "Default")
      (node (ref "U7") (pin "13") (pinfunction "13_13") (pintype "passive"))
    )
    (net (code "77") (name "unconnected-(U7-Pad14)") (class "Default")
      (node (ref "U7") (pin "14") (pinfunction "14_14") (pintype "passive"))
    )
    (net (code "78") (name "unconnected-(U7-Pad15)") (class "Default")
      (node (ref "U7") (pin "15") (pinfunction "15_15") (pintype "passive"))
    )
  )
)
